# 3PDT_Breakout.net
KiCad netlist of a schematic drawn in EAGLE
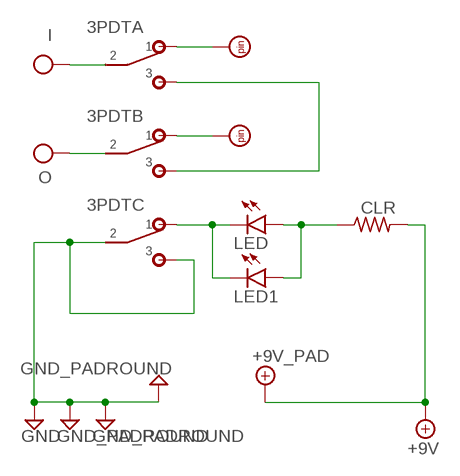
[diagram p0: schematic, sheet 1]

(export (version "E")
  (design (tool "Eeschema 10.0.6"))
  (components
    (comp (ref "3PDT")
      (value "3PDT")
      (footprint "eagle-import:3PDT")
      (libsource (lib "eagle-import") (part "3PDT"))
    )
    (comp (ref "CI")
      (value "PADS.SQR_NL")
      (footprint "eagle-import:PAD4")
      (libsource (lib "eagle-import") (part "PADS.SQR_NL"))
    )
    (comp (ref "CLR")
      (value "RESISTORS.3B")
      (footprint "eagle-import:R0207_3")
      (libsource (lib "eagle-import") (part "RESISTORS.3B"))
    )
    (comp (ref "CO")
      (value "PADS.SQR_NL")
      (footprint "eagle-import:PAD4")
      (libsource (lib "eagle-import") (part "PADS.SQR_NL"))
    )
    (comp (ref "GI")
      (value "GND_PADROUND")
      (footprint "eagle-import:ROUND")
      (libsource (lib "eagle-import") (part "GND_PADROUND"))
    )
    (comp (ref "GND")
      (value "GND_PADROUND")
      (footprint "eagle-import:ROUND")
      (libsource (lib "eagle-import") (part "GND_PADROUND"))
    )
    (comp (ref "GO")
      (value "GND_PADROUND")
      (footprint "eagle-import:ROUND")
      (libsource (lib "eagle-import") (part "GND_PADROUND"))
    )
    (comp (ref "I")
      (value "IN")
      (footprint "eagle-import:SQUARE")
      (libsource (lib "eagle-import") (part "IN"))
    )
    (comp (ref "LED")
      (value "LED3MM")
      (footprint "eagle-import:LED3MM")
      (libsource (lib "eagle-import") (part "LED3MM"))
    )
    (comp (ref "LED1")
      (value "LED3MM")
      (footprint "eagle-import:LED3MM")
      (libsource (lib "eagle-import") (part "LED3MM"))
    )
    (comp (ref "O")
      (value "OUT")
      (footprint "eagle-import:SQUARE")
      (libsource (lib "eagle-import") (part "OUT"))
    )
    (comp (ref "V+")
      (value "+9V_PAD")
      (footprint "eagle-import:SQUARE")
      (libsource (lib "eagle-import") (part "+9V_PAD"))
    )
  )
  (nets
    (net (code "1") (name "+9V") (class "Default")
      (node (ref "CLR") (pin "2") (pinfunction "2_2") (pintype "passive"))
      (node (ref "V+") (pin "1") (pinfunction "+9V_1") (pintype "power_in"))
    )
    (net (code "2") (name "GND") (class "Default")
      (node (ref "3PDT") (pin "C2") (pinfunction "2_C2") (pintype "passive"))
      (node (ref "3PDT") (pin "C3") (pinfunction "3_C3") (pintype "passive"))
      (node (ref "GI") (pin "1") (pinfunction "GND_1") (pintype "power_in"))
      (node (ref "GND") (pin "1") (pinfunction "GND_1") (pintype "power_in"))
      (node (ref "GO") (pin "1") (pinfunction "GND_1") (pintype "power_in"))
    )
    (net (code "3") (name "IN") (class "Default")
      (node (ref "3PDT") (pin "A2") (pinfunction "2_A2") (pintype "passive"))
      (node (ref "I") (pin "1") (pinfunction "IN_1") (pintype "power_in"))
    )
    (net (code "4") (name "Net-(3PDTA-1)") (class "Default")
      (node (ref "3PDT") (pin "A1") (pinfunction "1_A1") (pintype "passive"))
      (node (ref "CI") (pin "P$1") (pinfunction "P$1_P$1") (pintype "bidirectional"))
    )
    (net (code "5") (name "Net-(3PDTA-3)") (class "Default")
      (node (ref "3PDT") (pin "A3") (pinfunction "3_A3") (pintype "passive"))
      (node (ref "3PDT") (pin "B3") (pinfunction "3_B3") (pintype "passive"))
    )
    (net (code "6") (name "Net-(3PDTB-1)") (class "Default")
      (node (ref "3PDT") (pin "B1") (pinfunction "1_B1") (pintype "passive"))
      (node (ref "CO") (pin "P$1") (pinfunction "P$1_P$1") (pintype "bidirectional"))
    )
    (net (code "7") (name "Net-(3PDTC-1)") (class "Default")
      (node (ref "3PDT") (pin "C1") (pinfunction "1_C1") (pintype "passive"))
      (node (ref "LED") (pin "K") (pinfunction "C_K") (pintype "passive"))
      (node (ref "LED1") (pin "K") (pinfunction "C_K") (pintype "passive"))
    )
    (net (code "8") (name "Net-(CLR-Pad1)") (class "Default")
      (node (ref "CLR") (pin "1") (pinfunction "1_1") (pintype "passive"))
      (node (ref "LED") (pin "A") (pinfunction "A_A") (pintype "passive"))
      (node (ref "LED1") (pin "A") (pinfunction "A_A") (pintype "passive"))
    )
    (net (code "9") (name "OUT") (class "Default")
      (node (ref "3PDT") (pin "B2") (pinfunction "2_B2") (pintype "passive"))
      (node (ref "O") (pin "1") (pinfunction "OUT_1") (pintype "power_in"))
    )
  )
)
